# goodfet32.net
KiCad netlist of a schematic drawn in EAGLE
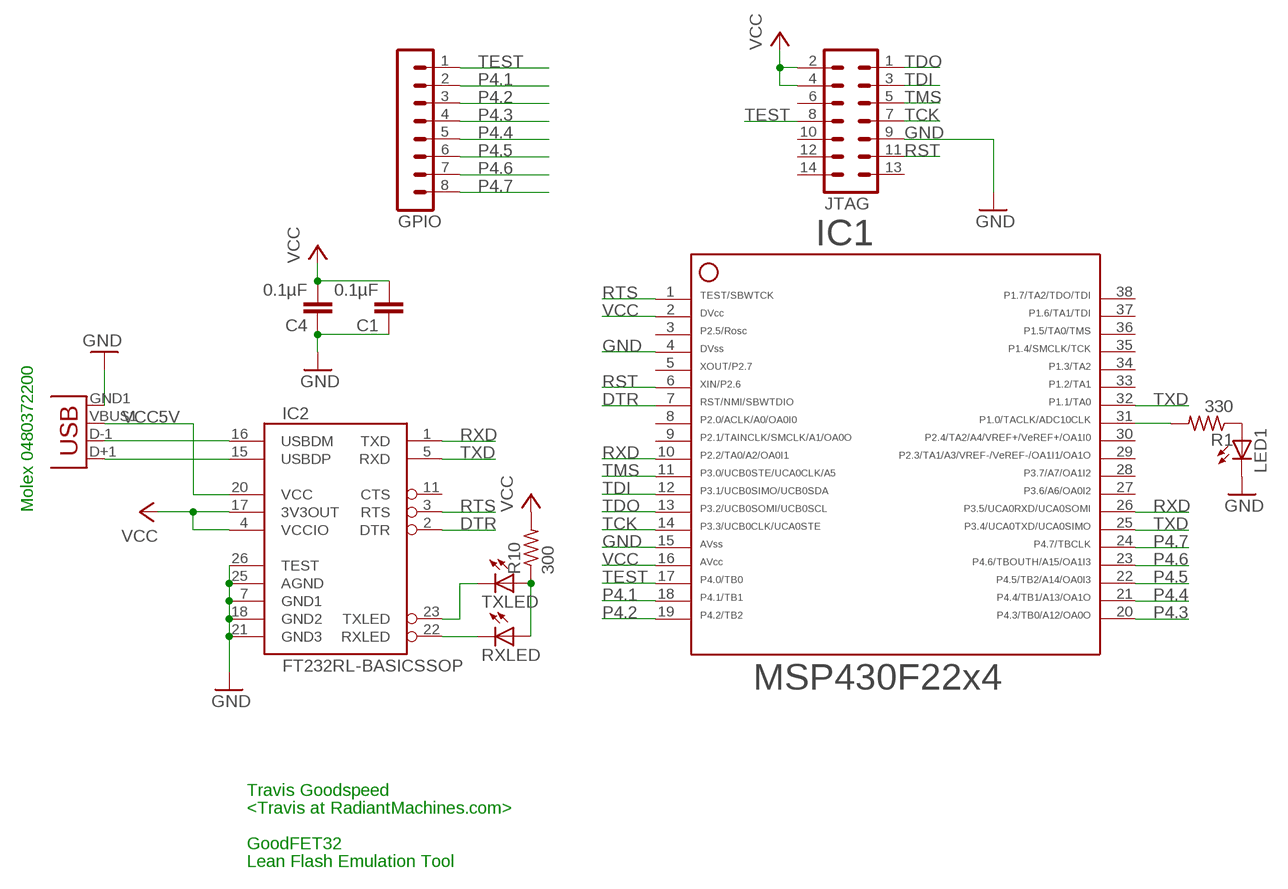
[diagram p0: schematic, sheet 1]

(export (version "E")
  (design (tool "Eeschema 10.0.6"))
  (components
    (comp (ref "C1")
      (value "0.1µF")
      (footprint "eagle-import:C0603")
      (libsource (lib "eagle-import") (part "C-EUC0603"))
    )
    (comp (ref "C4")
      (value "0.1µF")
      (footprint "eagle-import:C0603")
      (libsource (lib "eagle-import") (part "C-EUC0603"))
    )
    (comp (ref "GPIO")
      (value "MA08-1")
      (footprint "eagle-import:MA08-1")
      (libsource (lib "eagle-import") (part "MA08-1"))
    )
    (comp (ref "IC1")
      (value "F22X4---DA38")
      (footprint "eagle-import:DA38")
      (libsource (lib "eagle-import") (part "F22X4---DA38"))
    )
    (comp (ref "IC2")
      (value "FT232RL-BASICSSOP")
      (footprint "eagle-import:SSOP28DB")
      (libsource (lib "eagle-import") (part "FT232RL-BASICSSOP"))
    )
    (comp (ref "JP1")
      (value "USBA-SMD-MALE")
      (footprint "eagle-import:USB-A-SMT-MALE")
      (libsource (lib "eagle-import") (part "USBA-SMD-MALE"))
    )
    (comp (ref "JTAG")
      (value "MA07-2")
      (footprint "eagle-import:MA07-2")
      (libsource (lib "eagle-import") (part "MA07-2"))
    )
    (comp (ref "LED1")
      (value "LEDCHIP-LED0603")
      (footprint "eagle-import:CHIP-LED0603")
      (libsource (lib "eagle-import") (part "LEDCHIP-LED0603"))
    )
    (comp (ref "R1")
      (value "330")
      (footprint "eagle-import:R0603")
      (libsource (lib "eagle-import") (part "R-US_R0603"))
    )
    (comp (ref "R10")
      (value "300")
      (footprint "eagle-import:R0603")
      (libsource (lib "eagle-import") (part "R-US_R0603"))
    )
    (comp (ref "RXLED")
      (value "LEDCHIP-LED0603")
      (footprint "eagle-import:CHIP-LED0603")
      (libsource (lib "eagle-import") (part "LEDCHIP-LED0603"))
    )
    (comp (ref "TXLED")
      (value "LEDCHIP-LED0603")
      (footprint "eagle-import:CHIP-LED0603")
      (libsource (lib "eagle-import") (part "LEDCHIP-LED0603"))
    )
  )
  (nets
    (net (code "1") (name "/DTR") (class "Default")
      (node (ref "IC1") (pin "7") (pinfunction "7_7") (pintype "bidirectional"))
      (node (ref "IC2") (pin "2") (pinfunction "DTR_2") (pintype "bidirectional"))
    )
    (net (code "2") (name "/P4.1") (class "Default")
      (node (ref "GPIO") (pin "2") (pinfunction "2_2") (pintype "passive"))
      (node (ref "IC1") (pin "18") (pinfunction "18_18") (pintype "bidirectional"))
    )
    (net (code "3") (name "/P4.2") (class "Default")
      (node (ref "GPIO") (pin "3") (pinfunction "3_3") (pintype "passive"))
      (node (ref "IC1") (pin "19") (pinfunction "19_19") (pintype "bidirectional"))
    )
    (net (code "4") (name "/P4.3") (class "Default")
      (node (ref "GPIO") (pin "4") (pinfunction "4_4") (pintype "passive"))
      (node (ref "IC1") (pin "20") (pinfunction "20_20") (pintype "bidirectional"))
    )
    (net (code "5") (name "/P4.4") (class "Default")
      (node (ref "GPIO") (pin "5") (pinfunction "5_5") (pintype "passive"))
      (node (ref "IC1") (pin "21") (pinfunction "21_21") (pintype "bidirectional"))
    )
    (net (code "6") (name "/P4.5") (class "Default")
      (node (ref "GPIO") (pin "6") (pinfunction "6_6") (pintype "passive"))
      (node (ref "IC1") (pin "22") (pinfunction "22_22") (pintype "bidirectional"))
    )
    (net (code "7") (name "/P4.6") (class "Default")
      (node (ref "GPIO") (pin "7") (pinfunction "7_7") (pintype "passive"))
      (node (ref "IC1") (pin "23") (pinfunction "23_23") (pintype "bidirectional"))
    )
    (net (code "8") (name "/P4.7") (class "Default")
      (node (ref "GPIO") (pin "8") (pinfunction "8_8") (pintype "passive"))
      (node (ref "IC1") (pin "24") (pinfunction "24_24") (pintype "bidirectional"))
    )
    (net (code "9") (name "/RST") (class "Default")
      (node (ref "IC1") (pin "6") (pinfunction "6_6") (pintype "bidirectional"))
      (node (ref "JTAG") (pin "11") (pinfunction "11_11") (pintype "passive"))
    )
    (net (code "10") (name "/RTS") (class "Default")
      (node (ref "IC1") (pin "1") (pinfunction "1_1") (pintype "input"))
      (node (ref "IC2") (pin "3") (pinfunction "RTS_3") (pintype "bidirectional"))
    )
    (net (code "11") (name "/RXD") (class "Default")
      (node (ref "IC1") (pin "10") (pinfunction "10_10") (pintype "bidirectional"))
      (node (ref "IC1") (pin "26") (pinfunction "26_26") (pintype "bidirectional"))
      (node (ref "IC2") (pin "1") (pinfunction "TXD_1") (pintype "output"))
    )
    (net (code "12") (name "/TCK") (class "Default")
      (node (ref "IC1") (pin "14") (pinfunction "14_14") (pintype "bidirectional"))
      (node (ref "JTAG") (pin "7") (pinfunction "7_7") (pintype "passive"))
    )
    (net (code "13") (name "/TDI") (class "Default")
      (node (ref "IC1") (pin "12") (pinfunction "12_12") (pintype "bidirectional"))
      (node (ref "JTAG") (pin "3") (pinfunction "3_3") (pintype "passive"))
    )
    (net (code "14") (name "/TDO") (class "Default")
      (node (ref "IC1") (pin "13") (pinfunction "13_13") (pintype "bidirectional"))
      (node (ref "JTAG") (pin "1") (pinfunction "1_1") (pintype "passive"))
    )
    (net (code "15") (name "/TEST") (class "Default")
      (node (ref "GPIO") (pin "1") (pinfunction "1_1") (pintype "passive"))
      (node (ref "IC1") (pin "17") (pinfunction "17_17") (pintype "bidirectional"))
      (node (ref "JTAG") (pin "8") (pinfunction "8_8") (pintype "passive"))
    )
    (net (code "16") (name "/TMS") (class "Default")
      (node (ref "IC1") (pin "11") (pinfunction "11_11") (pintype "bidirectional"))
      (node (ref "JTAG") (pin "5") (pinfunction "5_5") (pintype "passive"))
    )
    (net (code "17") (name "/TXD") (class "Default")
      (node (ref "IC1") (pin "25") (pinfunction "25_25") (pintype "bidirectional"))
      (node (ref "IC1") (pin "32") (pinfunction "32_32") (pintype "bidirectional"))
      (node (ref "IC2") (pin "5") (pinfunction "RXD_5") (pintype "input"))
    )
    (net (code "18") (name "/VCC5V") (class "Default")
      (node (ref "IC2") (pin "20") (pinfunction "VCC_20") (pintype "power_in"))
      (node (ref "JP1") (pin "VBUS1") (pinfunction "VBUS_VBUS1") (pintype "bidirectional"))
    )
    (net (code "19") (name "GND") (class "Default")
      (node (ref "C1") (pin "1") (pinfunction "1_1") (pintype "passive"))
      (node (ref "C4") (pin "1") (pinfunction "1_1") (pintype "passive"))
      (node (ref "IC1") (pin "15") (pinfunction "15_15") (pintype "power_in"))
      (node (ref "IC1") (pin "4") (pinfunction "4_4") (pintype "power_in"))
      (node (ref "IC2") (pin "18") (pinfunction "GND2_18") (pintype "power_in"))
      (node (ref "IC2") (pin "21") (pinfunction "GND3_21") (pintype "power_in"))
      (node (ref "IC2") (pin "25") (pinfunction "AGND_25") (pintype "power_in"))
      (node (ref "IC2") (pin "26") (pinfunction "TEST_26") (pintype "input"))
      (node (ref "IC2") (pin "7") (pinfunction "GND1_7") (pintype "power_in"))
      (node (ref "JP1") (pin "GND1") (pinfunction "GND_GND1") (pintype "bidirectional"))
      (node (ref "JTAG") (pin "9") (pinfunction "9_9") (pintype "passive"))
      (node (ref "LED1") (pin "C") (pinfunction "C_C") (pintype "passive"))
    )
    (net (code "20") (name "Net-(IC1-Pad31)") (class "Default")
      (node (ref "IC1") (pin "31") (pinfunction "31_31") (pintype "bidirectional"))
      (node (ref "R1") (pin "2") (pinfunction "2_2") (pintype "passive"))
    )
    (net (code "21") (name "Net-(IC2-RXLED)") (class "Default")
      (node (ref "IC2") (pin "22") (pinfunction "RXLED_22") (pintype "bidirectional"))
      (node (ref "RXLED") (pin "C") (pinfunction "C_C") (pintype "passive"))
    )
    (net (code "22") (name "Net-(IC2-TXLED)") (class "Default")
      (node (ref "IC2") (pin "23") (pinfunction "TXLED_23") (pintype "bidirectional"))
      (node (ref "TXLED") (pin "C") (pinfunction "C_C") (pintype "passive"))
    )
    (net (code "23") (name "Net-(IC2-USBDM)") (class "Default")
      (node (ref "IC2") (pin "16") (pinfunction "USBDM_16") (pintype "bidirectional"))
      (node (ref "JP1") (pin "D-1") (pinfunction "D-_D-1") (pintype "bidirectional"))
    )
    (net (code "24") (name "Net-(IC2-USBDP)") (class "Default")
      (node (ref "IC2") (pin "15") (pinfunction "USBDP_15") (pintype "bidirectional"))
      (node (ref "JP1") (pin "D+1") (pinfunction "D+_D+1") (pintype "bidirectional"))
    )
    (net (code "25") (name "Net-(LED1-PadA)") (class "Default")
      (node (ref "LED1") (pin "A") (pinfunction "A_A") (pintype "passive"))
      (node (ref "R1") (pin "1") (pinfunction "1_1") (pintype "passive"))
    )
    (net (code "26") (name "Net-(R10-Pad1)") (class "Default")
      (node (ref "R10") (pin "1") (pinfunction "1_1") (pintype "passive"))
      (node (ref "RXLED") (pin "A") (pinfunction "A_A") (pintype "passive"))
      (node (ref "TXLED") (pin "A") (pinfunction "A_A") (pintype "passive"))
    )
    (net (code "27") (name "VCC") (class "Default")
      (node (ref "C1") (pin "2") (pinfunction "2_2") (pintype "passive"))
      (node (ref "C4") (pin "2") (pinfunction "2_2") (pintype "passive"))
      (node (ref "IC1") (pin "16") (pinfunction "16_16") (pintype "power_in"))
      (node (ref "IC1") (pin "2") (pinfunction "2_2") (pintype "power_in"))
      (node (ref "IC2") (pin "17") (pinfunction "3V3OUT_17") (pintype "output"))
      (node (ref "IC2") (pin "4") (pinfunction "VCCIO_4") (pintype "power_in"))
      (node (ref "JTAG") (pin "2") (pinfunction "2_2") (pintype "passive"))
      (node (ref "JTAG") (pin "4") (pinfunction "4_4") (pintype "passive"))
      (node (ref "R10") (pin "2") (pinfunction "2_2") (pintype "passive"))
    )
    (net (code "28") (name "unconnected-(IC1-Pad3)") (class "Default")
      (node (ref "IC1") (pin "3") (pinfunction "3_3") (pintype "bidirectional"))
    )
    (net (code "29") (name "unconnected-(IC1-Pad5)") (class "Default")
      (node (ref "IC1") (pin "5") (pinfunction "5_5") (pintype "bidirectional"))
    )
    (net (code "30") (name "unconnected-(IC1-Pad8)") (class "Default")
      (node (ref "IC1") (pin "8") (pinfunction "8_8") (pintype "bidirectional"))
    )
    (net (code "31") (name "unconnected-(IC1-Pad9)") (class "Default")
      (node (ref "IC1") (pin "9") (pinfunction "9_9") (pintype "bidirectional"))
    )
    (net (code "32") (name "unconnected-(IC1-Pad27)") (class "Default")
      (node (ref "IC1") (pin "27") (pinfunction "27_27") (pintype "bidirectional"))
    )
    (net (code "33") (name "unconnected-(IC1-Pad28)") (class "Default")
      (node (ref "IC1") (pin "28") (pinfunction "28_28") (pintype "bidirectional"))
    )
    (net (code "34") (name "unconnected-(IC1-Pad29)") (class "Default")
      (node (ref "IC1") (pin "29") (pinfunction "29_29") (pintype "bidirectional"))
    )
    (net (code "35") (name "unconnected-(IC1-Pad30)") (class "Default")
      (node (ref "IC1") (pin "30") (pinfunction "30_30") (pintype "bidirectional"))
    )
    (net (code "36") (name "unconnected-(IC1-Pad33)") (class "Default")
      (node (ref "IC1") (pin "33") (pinfunction "33_33") (pintype "bidirectional"))
    )
    (net (code "37") (name "unconnected-(IC1-Pad34)") (class "Default")
      (node (ref "IC1") (pin "34") (pinfunction "34_34") (pintype "bidirectional"))
    )
    (net (code "38") (name "unconnected-(IC1-Pad35)") (class "Default")
      (node (ref "IC1") (pin "35") (pinfunction "35_35") (pintype "bidirectional"))
    )
    (net (code "39") (name "unconnected-(IC1-Pad36)") (class "Default")
      (node (ref "IC1") (pin "36") (pinfunction "36_36") (pintype "bidirectional"))
    )
    (net (code "40") (name "unconnected-(IC1-Pad37)") (class "Default")
      (node (ref "IC1") (pin "37") (pinfunction "37_37") (pintype "bidirectional"))
    )
    (net (code "41") (name "unconnected-(IC1-Pad38)") (class "Default")
      (node (ref "IC1") (pin "38") (pinfunction "38_38") (pintype "bidirectional"))
    )
    (net (code "42") (name "unconnected-(IC2-CTS-Pad11)") (class "Default")
      (node (ref "IC2") (pin "11") (pinfunction "CTS_11") (pintype "bidirectional"))
    )
    (net (code "43") (name "unconnected-(JTAG-Pad6)") (class "Default")
      (node (ref "JTAG") (pin "6") (pinfunction "6_6") (pintype "passive"))
    )
    (net (code "44") (name "unconnected-(JTAG-Pad10)") (class "Default")
      (node (ref "JTAG") (pin "10") (pinfunction "10_10") (pintype "passive"))
    )
    (net (code "45") (name "unconnected-(JTAG-Pad12)") (class "Default")
      (node (ref "JTAG") (pin "12") (pinfunction "12_12") (pintype "passive"))
    )
    (net (code "46") (name "unconnected-(JTAG-Pad13)") (class "Default")
      (node (ref "JTAG") (pin "13") (pinfunction "13_13") (pintype "passive"))
    )
    (net (code "47") (name "unconnected-(JTAG-Pad14)") (class "Default")
      (node (ref "JTAG") (pin "14") (pinfunction "14_14") (pintype "passive"))
    )
  )
)
